# Audio.net
KiCad netlist of a schematic drawn in Altium Designer
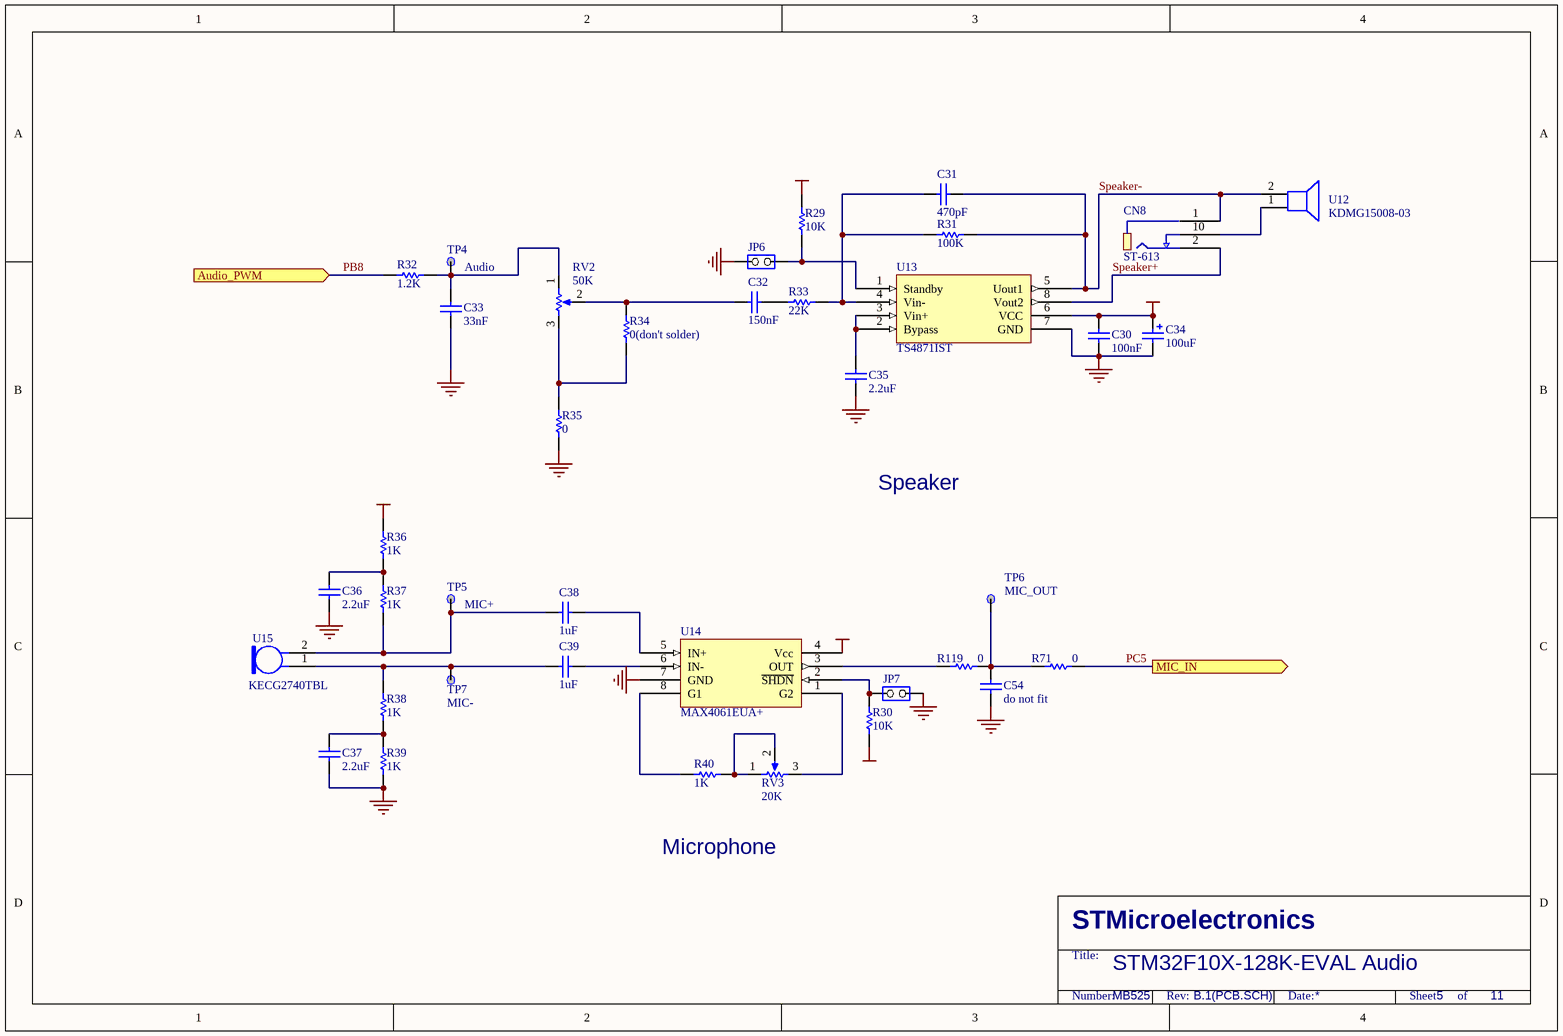
[diagram p0: Audio.SchDoc]

(export (version "E")
  (design (tool "Eeschema 10.0.6"))
  (components
    (comp (ref "C30")
      (value "100nF")
      (footprint "0603P")
      (description "Capacitor")
      (fields (field (name "PUBLISHER") "Altium Limited"))
      (libsource (lib "Miscellaneous Devices") (part "CAP"))
    )
    (comp (ref "C31")
      (value "470pF")
      (description "Capacitor")
      (fields (field (name "PUBLISHER") "Altium Limited"))
      (libsource (lib "Miscellaneous Devices") (part "CAP"))
    )
    (comp (ref "C32")
      (value "150nF")
      (description "Capacitor")
      (fields (field (name "PUBLISHER") "Altium Limited"))
      (libsource (lib "Miscellaneous Devices") (part "CAP"))
    )
    (comp (ref "C33")
      (value "33nF")
      (description "Capacitor")
      (fields (field (name "PUBLISHER") "Altium Limited"))
      (libsource (lib "Miscellaneous Devices") (part "CAP"))
    )
    (comp (ref "C34")
      (value "100uF")
      (footprint "TAN-B")
      (description "Polarized Capacitor (Radial)")
      (fields (field (name "PUBLISHER") "Altium Limited"))
      (libsource (lib "Miscellaneous Devices") (part "Cap Pol1"))
    )
    (comp (ref "C35")
      (value "2.2uF")
      (footprint "0805")
      (description "Capacitor")
      (fields (field (name "PUBLISHER") "Altium Limited"))
      (libsource (lib "Miscellaneous Devices") (part "CAP"))
    )
    (comp (ref "C36")
      (value "2.2uF")
      (footprint "0805")
      (description "Capacitor")
      (fields (field (name "PUBLISHER") "Altium Limited"))
      (libsource (lib "Miscellaneous Devices") (part "CAP"))
    )
    (comp (ref "C37")
      (value "2.2uF")
      (footprint "0805")
      (description "Capacitor")
      (fields (field (name "PUBLISHER") "Altium Limited"))
      (libsource (lib "Miscellaneous Devices") (part "CAP"))
    )
    (comp (ref "C38")
      (value "1uF")
      (description "Capacitor")
      (fields (field (name "PUBLISHER") "Altium Limited"))
      (libsource (lib "Miscellaneous Devices") (part "CAP"))
    )
    (comp (ref "C39")
      (value "1uF")
      (description "Capacitor")
      (fields (field (name "PUBLISHER") "Altium Limited"))
      (libsource (lib "Miscellaneous Devices") (part "CAP"))
    )
    (comp (ref "C54")
      (value "do not fit")
      (description "Capacitor")
      (fields (field (name "PUBLISHER") "Altium Limited"))
      (libsource (lib "Miscellaneous Devices") (part "CAP"))
    )
    (comp (ref "CN8") (value "ST-613") (footprint "PJST-613") (libsource (lib "MB469") (part "ST-613")))
    (comp (ref "JP6") (value "~") (footprint "SIP2") (libsource (lib "*") (part "JP2")))
    (comp (ref "JP7") (value "~") (footprint "SIP2") (libsource (lib "*") (part "JP2")))
    (comp (ref "R29")
      (value "10K")
      (description "Resistor")
      (fields (field (name "PUBLISHER") "Altium Limited"))
      (libsource (lib "Miscellaneous Devices") (part "Res1"))
    )
    (comp (ref "R30")
      (value "10K")
      (description "Resistor")
      (fields (field (name "PUBLISHER") "Altium Limited"))
      (libsource (lib "Miscellaneous Devices") (part "Res1"))
    )
    (comp (ref "R31")
      (value "100K")
      (description "Resistor")
      (fields (field (name "PUBLISHER") "Altium Limited"))
      (libsource (lib "Miscellaneous Devices") (part "Res1"))
    )
    (comp (ref "R32")
      (value "1.2K")
      (description "Resistor")
      (fields (field (name "PUBLISHER") "Altium Limited"))
      (libsource (lib "Miscellaneous Devices") (part "Res1"))
    )
    (comp (ref "R33")
      (value "22K")
      (description "Resistor")
      (fields (field (name "PUBLISHER") "Altium Limited"))
      (libsource (lib "Miscellaneous Devices") (part "Res1"))
    )
    (comp (ref "R34")
      (value "0(don't solder)")
      (description "Resistor")
      (fields (field (name "PUBLISHER") "Altium Limited"))
      (libsource (lib "Miscellaneous Devices") (part "Res1"))
    )
    (comp (ref "R35")
      (value "0")
      (description "Resistor")
      (fields (field (name "PUBLISHER") "Altium Limited"))
      (libsource (lib "Miscellaneous Devices") (part "Res1"))
    )
    (comp (ref "R36")
      (value "1K")
      (description "Resistor")
      (fields (field (name "PUBLISHER") "Altium Limited"))
      (libsource (lib "Miscellaneous Devices") (part "Res1"))
    )
    (comp (ref "R37")
      (value "1K")
      (description "Resistor")
      (fields (field (name "PUBLISHER") "Altium Limited"))
      (libsource (lib "Miscellaneous Devices") (part "Res1"))
    )
    (comp (ref "R38")
      (value "1K")
      (description "Resistor")
      (fields (field (name "PUBLISHER") "Altium Limited"))
      (libsource (lib "Miscellaneous Devices") (part "Res1"))
    )
    (comp (ref "R39")
      (value "1K")
      (description "Resistor")
      (fields (field (name "PUBLISHER") "Altium Limited"))
      (libsource (lib "Miscellaneous Devices") (part "Res1"))
    )
    (comp (ref "R40")
      (value "1K")
      (description "Resistor")
      (fields (field (name "PUBLISHER") "Altium Limited"))
      (libsource (lib "Miscellaneous Devices") (part "Res1"))
    )
    (comp (ref "R71")
      (value "0")
      (description "Resistor")
      (fields (field (name "PUBLISHER") "Altium Limited"))
      (libsource (lib "Miscellaneous Devices") (part "Res1"))
    )
    (comp (ref "R119")
      (value "0")
      (description "Resistor")
      (fields (field (name "PUBLISHER") "Altium Limited"))
      (libsource (lib "Miscellaneous Devices") (part "Res1"))
    )
    (comp (ref "RV2") (value "50K") (footprint "3314-J") (libsource (lib "STR910_SCHLIB") (part "RV")))
    (comp (ref "RV3") (value "20K") (footprint "3314-J") (libsource (lib "STR910_SCHLIB") (part "RV")))
    (comp (ref "TP4") (value "Audio") (footprint "TP") (libsource (lib "*") (part "TP")))
    (comp (ref "TP5") (value "MIC+") (footprint "TP") (libsource (lib "*") (part "TP")))
    (comp (ref "TP6") (value "MIC_OUT") (footprint "TP") (libsource (lib "*") (part "TP")))
    (comp (ref "TP7") (value "MIC-") (footprint "TP") (libsource (lib "*") (part "TP")))
    (comp (ref "U12")
      (value "KDMG15008-03")
      (footprint "KS1508")
      (description "Loudspeaker")
      (fields (field (name "PUBLISHER") "Altium Limited"))
      (libsource (lib "Miscellaneous Devices") (part "Speaker"))
    )
    (comp (ref "U13")
      (value "TS4871IST")
      (footprint "TSSOP8")
      (libsource (lib "STR910_SCHLIB") (part "TS4871IST"))
    )
    (comp (ref "U14")
      (value "MAX4061EUA+")
      (footprint "tssop8")
      (libsource (lib "STR910_SCHLIB") (part "MAX4061EUA+"))
    )
    (comp (ref "U15")
      (value "KECG2740TBL")
      (footprint "KEC2740")
      (description "Microphone")
      (fields (field (name "PUBLISHER") "Altium Limited"))
      (libsource (lib "Miscellaneous Devices") (part "Mic2"))
    )
  )
  (nets
    (net (code "1") (name "+3V3") (class "Default")
      (node (ref "C30") (pin "2") (pinfunction "2_2") (pintype "passive"))
      (node (ref "C34") (pin "1") (pinfunction "1_1") (pintype "passive"))
      (node (ref "R29") (pin "2") (pinfunction "2_2") (pintype "passive"))
      (node (ref "R30") (pin "1") (pinfunction "1_1") (pintype "passive"))
      (node (ref "R36") (pin "2") (pinfunction "2_2") (pintype "passive"))
      (node (ref "U13") (pin "6") (pinfunction "VCC_6") (pintype "power_in"))
      (node (ref "U14") (pin "4") (pinfunction "Vcc_4") (pintype "power_in"))
    )
    (net (code "2") (name "/PB8") (class "Default")
      (node (ref "R32") (pin "1") (pinfunction "1_1") (pintype "passive"))
    )
    (net (code "3") (name "/PC5") (class "Default")
      (node (ref "R71") (pin "1") (pinfunction "1_1") (pintype "passive"))
    )
    (net (code "4") (name "/Speaker+") (class "Default")
      (node (ref "CN8") (pin "2") (pintype "passive"))
      (node (ref "U13") (pin "8") (pinfunction "Vout2_8") (pintype "output"))
    )
    (net (code "5") (name "/Speaker-") (class "Default")
      (node (ref "C31") (pin "2") (pinfunction "2_2") (pintype "passive"))
      (node (ref "CN8") (pin "1") (pintype "passive"))
      (node (ref "R31") (pin "2") (pinfunction "2_2") (pintype "passive"))
      (node (ref "U12") (pin "2") (pinfunction "--_2") (pintype "passive"))
      (node (ref "U13") (pin "5") (pinfunction "Uout1_5") (pintype "output"))
    )
    (net (code "6") (name "GND") (class "Default")
      (node (ref "C30") (pin "1") (pinfunction "1_1") (pintype "passive"))
      (node (ref "C33") (pin "1") (pinfunction "1_1") (pintype "passive"))
      (node (ref "C34") (pin "2") (pinfunction "2_2") (pintype "passive"))
      (node (ref "C35") (pin "2") (pinfunction "2_2") (pintype "passive"))
      (node (ref "C36") (pin "2") (pinfunction "2_2") (pintype "passive"))
      (node (ref "C37") (pin "2") (pinfunction "2_2") (pintype "passive"))
      (node (ref "C54") (pin "2") (pinfunction "2_2") (pintype "passive"))
      (node (ref "JP6") (pin "2") (pinfunction "NO_2") (pintype "passive"))
      (node (ref "JP7") (pin "2") (pinfunction "NO_2") (pintype "passive"))
      (node (ref "R35") (pin "1") (pinfunction "1_1") (pintype "passive"))
      (node (ref "R39") (pin "1") (pinfunction "1_1") (pintype "passive"))
      (node (ref "U13") (pin "7") (pinfunction "GND_7") (pintype "power_in"))
      (node (ref "U14") (pin "7") (pinfunction "GND_7") (pintype "power_in"))
    )
    (net (code "7") (name "Net-(C32-Pad2)") (class "Default")
      (node (ref "C32") (pin "2") (pinfunction "2_2") (pintype "passive"))
      (node (ref "R33") (pin "1") (pinfunction "1_1") (pintype "passive"))
    )
    (net (code "8") (name "Net-(C36-Pad1)") (class "Default")
      (node (ref "C36") (pin "1") (pinfunction "1_1") (pintype "passive"))
      (node (ref "R36") (pin "1") (pinfunction "1_1") (pintype "passive"))
      (node (ref "R37") (pin "1") (pinfunction "1_1") (pintype "passive"))
    )
    (net (code "9") (name "Net-(C37-Pad1)") (class "Default")
      (node (ref "C37") (pin "1") (pinfunction "1_1") (pintype "passive"))
      (node (ref "R38") (pin "1") (pinfunction "1_1") (pintype "passive"))
      (node (ref "R39") (pin "2") (pinfunction "2_2") (pintype "passive"))
    )
    (net (code "10") (name "Net-(C38-Pad1)") (class "Default")
      (node (ref "C38") (pin "1") (pinfunction "1_1") (pintype "passive"))
      (node (ref "R37") (pin "2") (pinfunction "2_2") (pintype "passive"))
      (node (ref "TP5") (pin "1") (pinfunction "1_1") (pintype "passive"))
      (node (ref "U15") (pin "2") (pinfunction "2_2") (pintype "passive"))
    )
    (net (code "11") (name "Net-(C39-Pad1)") (class "Default")
      (node (ref "C39") (pin "1") (pinfunction "1_1") (pintype "passive"))
      (node (ref "R38") (pin "2") (pinfunction "2_2") (pintype "passive"))
      (node (ref "TP7") (pin "1") (pinfunction "1_1") (pintype "passive"))
      (node (ref "U15") (pin "1") (pinfunction "1_1") (pintype "passive"))
    )
    (net (code "12") (name "Net-(C54-Pad1)") (class "Default")
      (node (ref "C54") (pin "1") (pinfunction "1_1") (pintype "passive"))
      (node (ref "R119") (pin "1") (pinfunction "1_1") (pintype "passive"))
      (node (ref "R71") (pin "2") (pinfunction "2_2") (pintype "passive"))
      (node (ref "TP6") (pin "1") (pinfunction "1_1") (pintype "passive"))
    )
    (net (code "13") (name "Net-(JP6-COMMON)") (class "Default")
      (node (ref "JP6") (pin "1") (pinfunction "COMMON_1") (pintype "passive"))
      (node (ref "R29") (pin "1") (pinfunction "1_1") (pintype "passive"))
      (node (ref "U13") (pin "1") (pinfunction "Standby_1") (pintype "input"))
    )
    (net (code "14") (name "Net-(JP7-COMMON)") (class "Default")
      (node (ref "JP7") (pin "1") (pinfunction "COMMON_1") (pintype "passive"))
      (node (ref "R30") (pin "2") (pinfunction "2_2") (pintype "passive"))
      (node (ref "U14") (pin "2") (pinfunction "~{SHDN}_2") (pintype "input"))
    )
    (net (code "15") (name "Net-(RV2-BOT)") (class "Default")
      (node (ref "C33") (pin "2") (pinfunction "2_2") (pintype "passive"))
      (node (ref "R32") (pin "2") (pinfunction "2_2") (pintype "passive"))
      (node (ref "RV2") (pin "1") (pinfunction "BOT_1") (pintype "passive"))
      (node (ref "TP4") (pin "1") (pinfunction "1_1") (pintype "passive"))
    )
    (net (code "16") (name "Net-(RV2-TAP)") (class "Default")
      (node (ref "C32") (pin "1") (pinfunction "1_1") (pintype "passive"))
      (node (ref "R34") (pin "2") (pinfunction "2_2") (pintype "passive"))
      (node (ref "RV2") (pin "2") (pinfunction "TAP_2") (pintype "passive"))
    )
    (net (code "17") (name "Net-(RV2-TOP)") (class "Default")
      (node (ref "R34") (pin "1") (pinfunction "1_1") (pintype "passive"))
      (node (ref "R35") (pin "2") (pinfunction "2_2") (pintype "passive"))
      (node (ref "RV2") (pin "3") (pinfunction "TOP_3") (pintype "passive"))
    )
    (net (code "18") (name "Net-(RV3-BOT)") (class "Default")
      (node (ref "R40") (pin "1") (pinfunction "1_1") (pintype "passive"))
      (node (ref "RV3") (pin "1") (pinfunction "BOT_1") (pintype "passive"))
      (node (ref "RV3") (pin "2") (pinfunction "TAP_2") (pintype "passive"))
    )
    (net (code "19") (name "Net-(RV3-TOP)") (class "Default")
      (node (ref "RV3") (pin "3") (pinfunction "TOP_3") (pintype "passive"))
      (node (ref "U14") (pin "1") (pinfunction "G2_1") (pintype "passive"))
    )
    (net (code "20") (name "Net-(U12-+)") (class "Default")
      (node (ref "CN8") (pin "10") (pintype "passive"))
      (node (ref "U12") (pin "1") (pinfunction "+_1") (pintype "passive"))
    )
    (net (code "21") (name "Net-(U13-Bypass)") (class "Default")
      (node (ref "C35") (pin "1") (pinfunction "1_1") (pintype "passive"))
      (node (ref "U13") (pin "2") (pinfunction "Bypass_2") (pintype "input"))
      (node (ref "U13") (pin "3") (pinfunction "Vin+_3") (pintype "input"))
    )
    (net (code "22") (name "Net-(U13-Vin-)") (class "Default")
      (node (ref "C31") (pin "1") (pinfunction "1_1") (pintype "passive"))
      (node (ref "R31") (pin "1") (pinfunction "1_1") (pintype "passive"))
      (node (ref "R33") (pin "2") (pinfunction "2_2") (pintype "passive"))
      (node (ref "U13") (pin "4") (pinfunction "Vin-_4") (pintype "input"))
    )
    (net (code "23") (name "Net-(U14-G1)") (class "Default")
      (node (ref "R40") (pin "2") (pinfunction "2_2") (pintype "passive"))
      (node (ref "U14") (pin "8") (pinfunction "G1_8") (pintype "passive"))
    )
    (net (code "24") (name "Net-(U14-IN+)") (class "Default")
      (node (ref "C38") (pin "2") (pinfunction "2_2") (pintype "passive"))
      (node (ref "U14") (pin "5") (pinfunction "IN+_5") (pintype "input"))
    )
    (net (code "25") (name "Net-(U14-IN-)") (class "Default")
      (node (ref "C39") (pin "2") (pinfunction "2_2") (pintype "passive"))
      (node (ref "U14") (pin "6") (pinfunction "IN-_6") (pintype "input"))
    )
    (net (code "26") (name "Net-(U14-OUT)") (class "Default")
      (node (ref "R119") (pin "2") (pinfunction "2_2") (pintype "passive"))
      (node (ref "U14") (pin "3") (pinfunction "OUT_3") (pintype "output"))
    )
  )
)
